# SCH_MCP3008-Raspberry-Pi-3B_-SPI_2025-04.net
KiCad netlist of a schematic drawn in EasyEDA
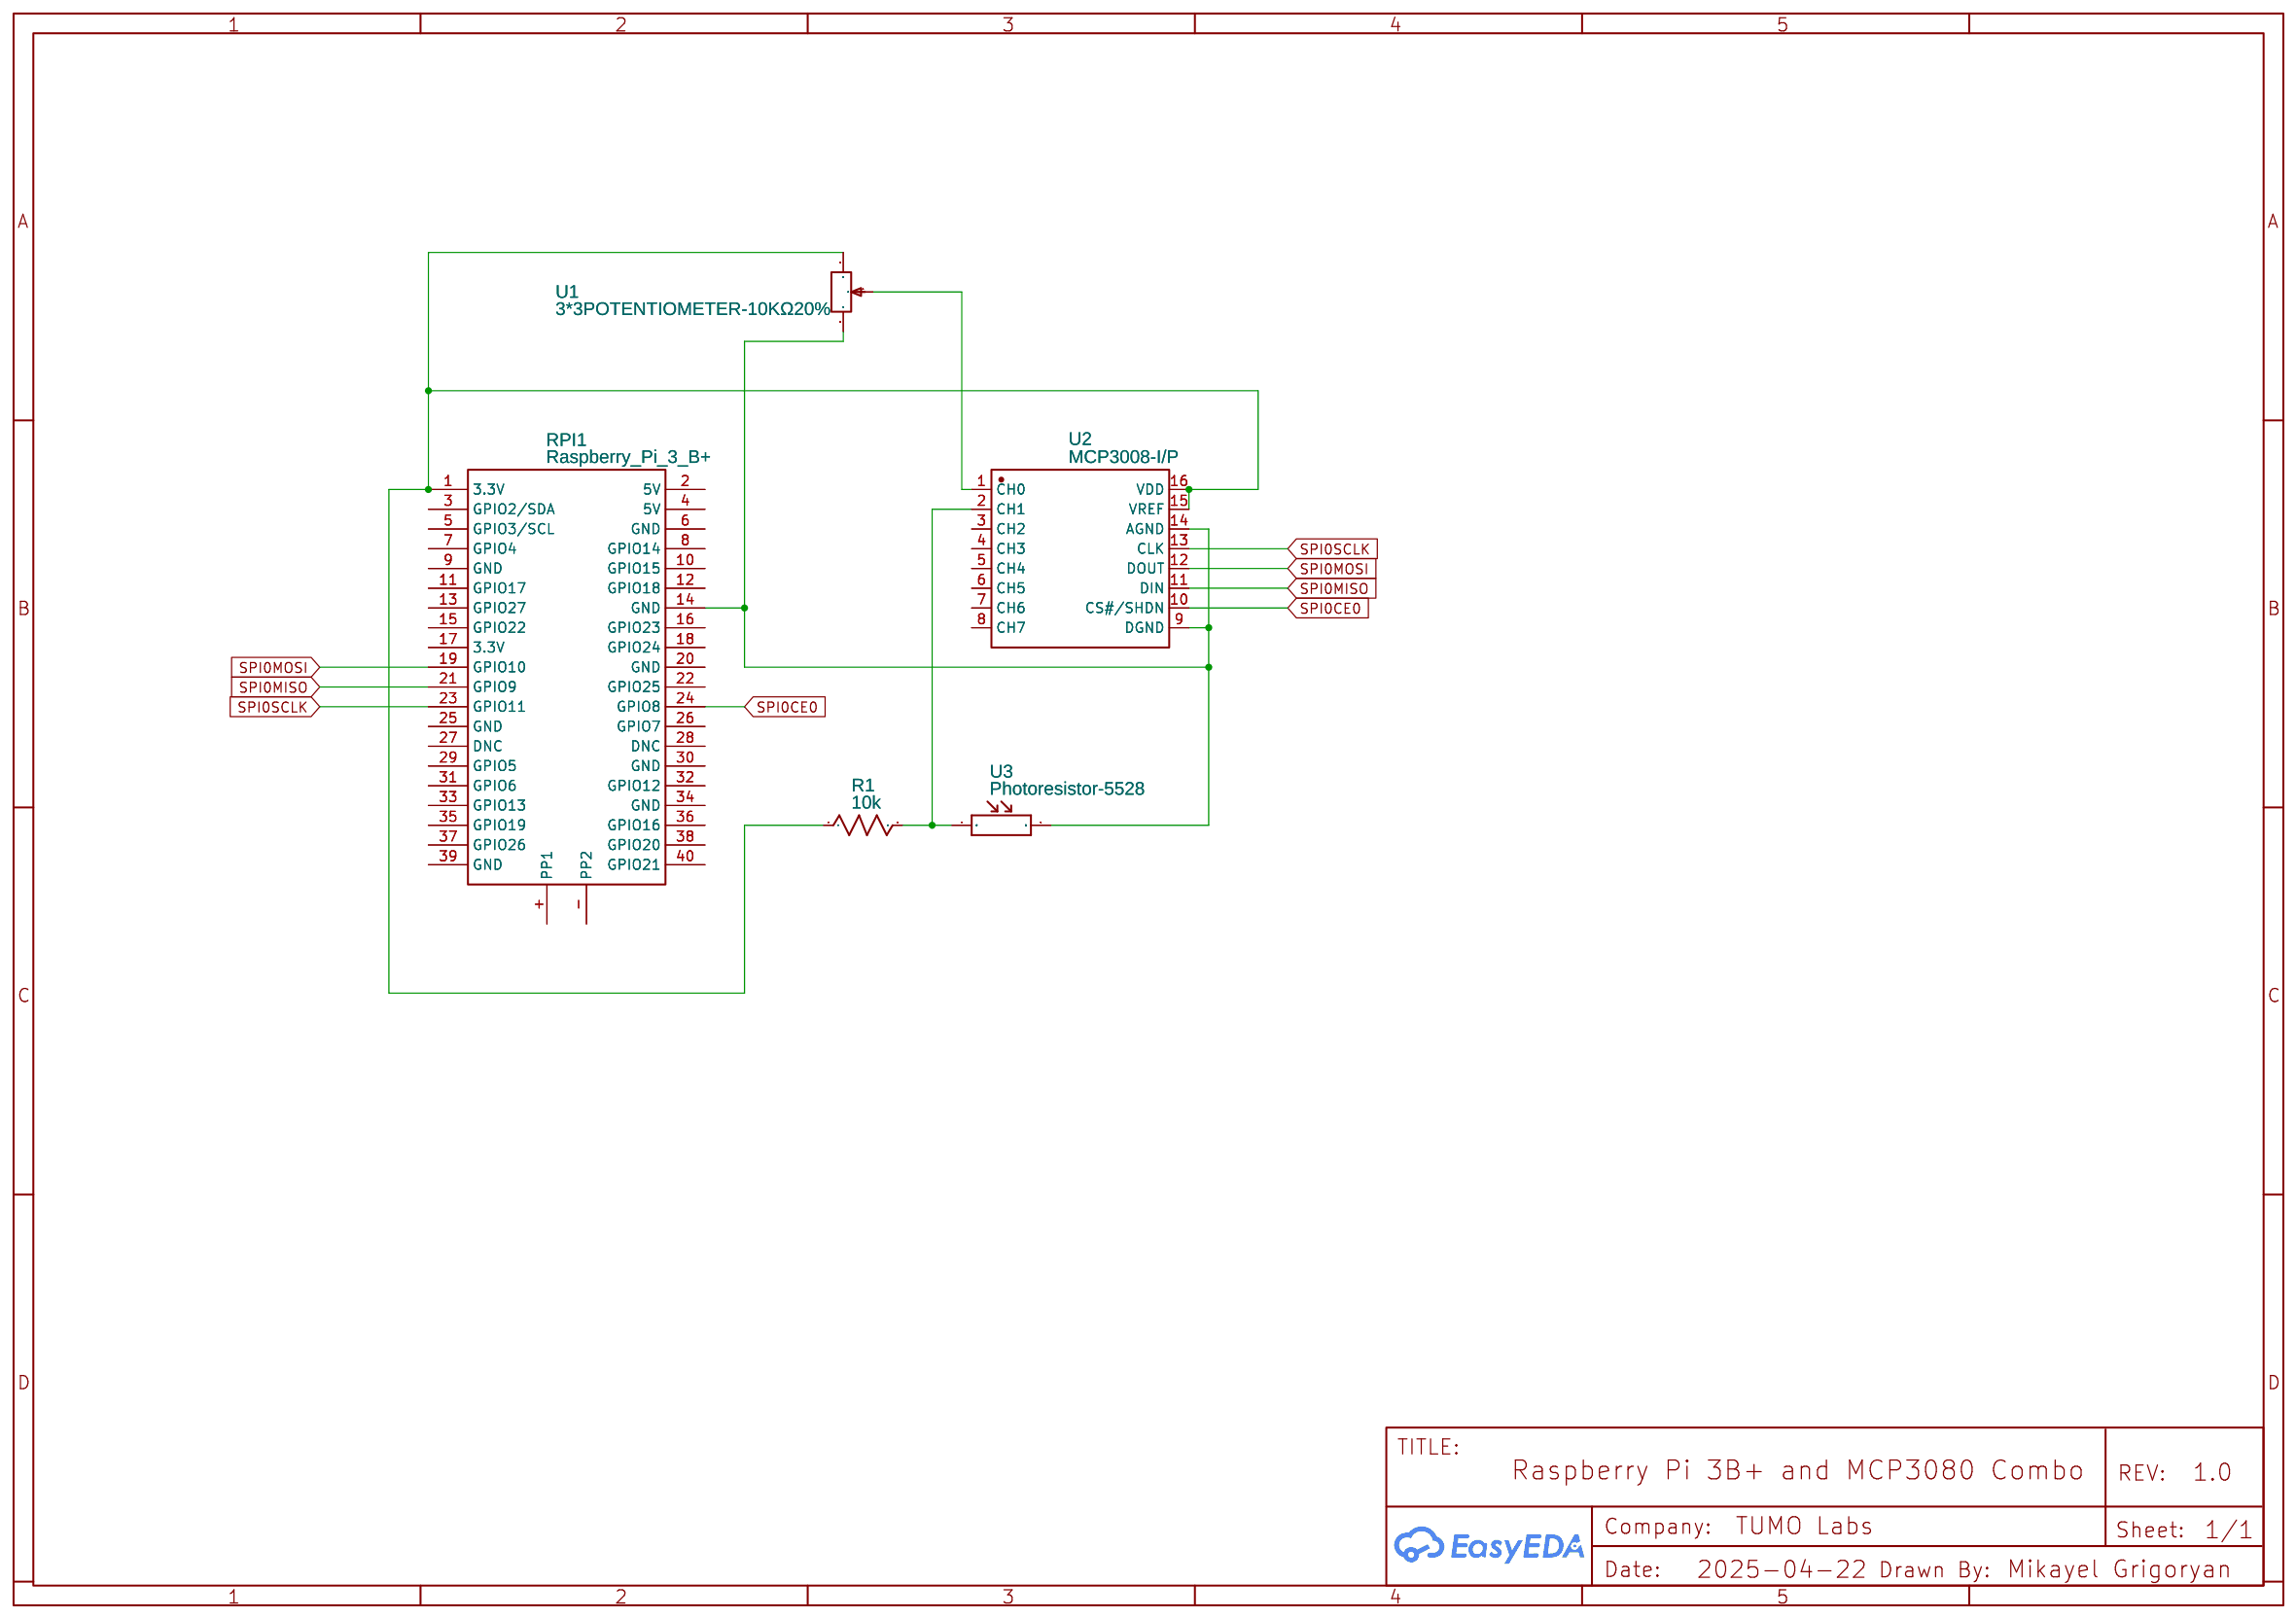
[diagram p0: schematic sheet]

(export (version "E")
  (design (tool "Eeschema 10.0.6"))
  (components
    (comp (ref "R1") (value "10k") (libsource (lib "") (part "R_0603_US")))
    (comp (ref "RPI1")
      (value "Raspberry_Pi_3_B+")
      (fields
        (field (name "Manufacturer Part") "Raspberry Pi 3 - Model B+ - 1.4GHz Cortex-A53 with 1GB RAM")
        (field (name "Manufacturer") "Raspberry Pi")
      )
      (libsource (lib "") (part "Raspberry_Pi_3_B+"))
    )
    (comp (ref "U1")
      (value "3*3POTENTIOMETER-10KΩ20%")
      (fields (field (name "Manufacturer Part") "3*3Potentiometer-10kΩ20%"))
      (libsource (lib "") (part "3*3POTENTIOMETER-10KΩ20%"))
    )
    (comp (ref "U2")
      (value "MCP3008-I/P")
      (fields (field (name "Manufacturer") "MICROCHIP(美国微芯)"))
      (libsource (lib "") (part "MCP3008-I/P"))
    )
    (comp (ref "U3") (value "Photoresistor-5528") (libsource (lib "") (part "Photoresistor-5528")))
  )
  (nets
    (net (code "1") (name "Net-(U2-AGND)") (class "Default")
      (node (ref "RPI1") (pin "14") (pinfunction "GND_14") (pintype "unspecified"))
      (node (ref "U1") (pin "3") (pinfunction "3_3") (pintype "input"))
      (node (ref "U2") (pin "14") (pinfunction "AGND_14") (pintype "unspecified"))
      (node (ref "U2") (pin "9") (pinfunction "DGND_9") (pintype "unspecified"))
      (node (ref "U3") (pin "2") (pinfunction "P$2_2") (pintype "unspecified"))
    )
    (net (code "2") (name "Net-(U2-CH0)") (class "Default")
      (node (ref "U1") (pin "2") (pinfunction "2_2") (pintype "input"))
      (node (ref "U2") (pin "1") (pinfunction "CH0_1") (pintype "unspecified"))
    )
    (net (code "3") (name "Net-(U2-CH1)") (class "Default")
      (node (ref "R1") (pin "2") (pinfunction "2_2") (pintype "unspecified"))
      (node (ref "U2") (pin "2") (pinfunction "CH1_2") (pintype "unspecified"))
      (node (ref "U3") (pin "1") (pinfunction "P$1_1") (pintype "unspecified"))
    )
    (net (code "4") (name "Net-(U2-VDD)") (class "Default")
      (node (ref "R1") (pin "1") (pinfunction "1_1") (pintype "unspecified"))
      (node (ref "RPI1") (pin "1") (pinfunction "3.3V_1") (pintype "passive"))
      (node (ref "U1") (pin "1") (pinfunction "1_1") (pintype "input"))
      (node (ref "U2") (pin "15") (pinfunction "VREF_15") (pintype "unspecified"))
      (node (ref "U2") (pin "16") (pinfunction "VDD_16") (pintype "unspecified"))
    )
    (net (code "5") (name "SPI0CE0") (class "Default")
      (node (ref "RPI1") (pin "24") (pinfunction "GPIO8_24") (pintype "bidirectional"))
      (node (ref "U2") (pin "10") (pinfunction "CS#/SHDN_10") (pintype "unspecified"))
    )
    (net (code "6") (name "SPI0MISO") (class "Default")
      (node (ref "RPI1") (pin "21") (pinfunction "GPIO9_21") (pintype "bidirectional"))
      (node (ref "U2") (pin "11") (pinfunction "DIN_11") (pintype "unspecified"))
    )
    (net (code "7") (name "SPI0MOSI") (class "Default")
      (node (ref "RPI1") (pin "19") (pinfunction "GPIO10_19") (pintype "bidirectional"))
      (node (ref "U2") (pin "12") (pinfunction "DOUT_12") (pintype "unspecified"))
    )
    (net (code "8") (name "SPI0SCLK") (class "Default")
      (node (ref "RPI1") (pin "23") (pinfunction "GPIO11_23") (pintype "bidirectional"))
      (node (ref "U2") (pin "13") (pinfunction "CLK_13") (pintype "unspecified"))
    )
    (net (code "9") (name "unconnected-(RPI1-3.3V-Pad17)") (class "Default")
      (node (ref "RPI1") (pin "17") (pinfunction "3.3V_17") (pintype "passive"))
    )
    (net (code "10") (name "unconnected-(RPI1-5V-Pad2)") (class "Default")
      (node (ref "RPI1") (pin "2") (pinfunction "5V_2") (pintype "passive"))
    )
    (net (code "11") (name "unconnected-(RPI1-5V-Pad4)") (class "Default")
      (node (ref "RPI1") (pin "4") (pinfunction "5V_4") (pintype "passive"))
    )
    (net (code "12") (name "unconnected-(RPI1-DNC-Pad27)") (class "Default")
      (node (ref "RPI1") (pin "27") (pinfunction "DNC_27") (pintype "unspecified"))
    )
    (net (code "13") (name "unconnected-(RPI1-DNC-Pad28)") (class "Default")
      (node (ref "RPI1") (pin "28") (pinfunction "DNC_28") (pintype "unspecified"))
    )
    (net (code "14") (name "unconnected-(RPI1-GND-Pad6)") (class "Default")
      (node (ref "RPI1") (pin "6") (pinfunction "GND_6") (pintype "unspecified"))
    )
    (net (code "15") (name "unconnected-(RPI1-GND-Pad9)") (class "Default")
      (node (ref "RPI1") (pin "9") (pinfunction "GND_9") (pintype "unspecified"))
    )
    (net (code "16") (name "unconnected-(RPI1-GND-Pad20)") (class "Default")
      (node (ref "RPI1") (pin "20") (pinfunction "GND_20") (pintype "unspecified"))
    )
    (net (code "17") (name "unconnected-(RPI1-GND-Pad25)") (class "Default")
      (node (ref "RPI1") (pin "25") (pinfunction "GND_25") (pintype "unspecified"))
    )
    (net (code "18") (name "unconnected-(RPI1-GND-Pad30)") (class "Default")
      (node (ref "RPI1") (pin "30") (pinfunction "GND_30") (pintype "unspecified"))
    )
    (net (code "19") (name "unconnected-(RPI1-GND-Pad34)") (class "Default")
      (node (ref "RPI1") (pin "34") (pinfunction "GND_34") (pintype "unspecified"))
    )
    (net (code "20") (name "unconnected-(RPI1-GND-Pad39)") (class "Default")
      (node (ref "RPI1") (pin "39") (pinfunction "GND_39") (pintype "unspecified"))
    )
    (net (code "21") (name "unconnected-(RPI1-GPIO2{slash}SDA-Pad3)") (class "Default")
      (node (ref "RPI1") (pin "3") (pinfunction "GPIO2/SDA_3") (pintype "bidirectional"))
    )
    (net (code "22") (name "unconnected-(RPI1-GPIO3{slash}SCL-Pad5)") (class "Default")
      (node (ref "RPI1") (pin "5") (pinfunction "GPIO3/SCL_5") (pintype "bidirectional"))
    )
    (net (code "23") (name "unconnected-(RPI1-GPIO4-Pad7)") (class "Default")
      (node (ref "RPI1") (pin "7") (pinfunction "GPIO4_7") (pintype "bidirectional"))
    )
    (net (code "24") (name "unconnected-(RPI1-GPIO5-Pad29)") (class "Default")
      (node (ref "RPI1") (pin "29") (pinfunction "GPIO5_29") (pintype "bidirectional"))
    )
    (net (code "25") (name "unconnected-(RPI1-GPIO6-Pad31)") (class "Default")
      (node (ref "RPI1") (pin "31") (pinfunction "GPIO6_31") (pintype "bidirectional"))
    )
    (net (code "26") (name "unconnected-(RPI1-GPIO7-Pad26)") (class "Default")
      (node (ref "RPI1") (pin "26") (pinfunction "GPIO7_26") (pintype "bidirectional"))
    )
    (net (code "27") (name "unconnected-(RPI1-GPIO12-Pad32)") (class "Default")
      (node (ref "RPI1") (pin "32") (pinfunction "GPIO12_32") (pintype "bidirectional"))
    )
    (net (code "28") (name "unconnected-(RPI1-GPIO13-Pad33)") (class "Default")
      (node (ref "RPI1") (pin "33") (pinfunction "GPIO13_33") (pintype "bidirectional"))
    )
    (net (code "29") (name "unconnected-(RPI1-GPIO14-Pad8)") (class "Default")
      (node (ref "RPI1") (pin "8") (pinfunction "GPIO14_8") (pintype "bidirectional"))
    )
    (net (code "30") (name "unconnected-(RPI1-GPIO15-Pad10)") (class "Default")
      (node (ref "RPI1") (pin "10") (pinfunction "GPIO15_10") (pintype "bidirectional"))
    )
    (net (code "31") (name "unconnected-(RPI1-GPIO16-Pad36)") (class "Default")
      (node (ref "RPI1") (pin "36") (pinfunction "GPIO16_36") (pintype "bidirectional"))
    )
    (net (code "32") (name "unconnected-(RPI1-GPIO17-Pad11)") (class "Default")
      (node (ref "RPI1") (pin "11") (pinfunction "GPIO17_11") (pintype "bidirectional"))
    )
    (net (code "33") (name "unconnected-(RPI1-GPIO18-Pad12)") (class "Default")
      (node (ref "RPI1") (pin "12") (pinfunction "GPIO18_12") (pintype "bidirectional"))
    )
    (net (code "34") (name "unconnected-(RPI1-GPIO19-Pad35)") (class "Default")
      (node (ref "RPI1") (pin "35") (pinfunction "GPIO19_35") (pintype "bidirectional"))
    )
    (net (code "35") (name "unconnected-(RPI1-GPIO20-Pad38)") (class "Default")
      (node (ref "RPI1") (pin "38") (pinfunction "GPIO20_38") (pintype "bidirectional"))
    )
    (net (code "36") (name "unconnected-(RPI1-GPIO21-Pad40)") (class "Default")
      (node (ref "RPI1") (pin "40") (pinfunction "GPIO21_40") (pintype "bidirectional"))
    )
    (net (code "37") (name "unconnected-(RPI1-GPIO22-Pad15)") (class "Default")
      (node (ref "RPI1") (pin "15") (pinfunction "GPIO22_15") (pintype "bidirectional"))
    )
    (net (code "38") (name "unconnected-(RPI1-GPIO23-Pad16)") (class "Default")
      (node (ref "RPI1") (pin "16") (pinfunction "GPIO23_16") (pintype "bidirectional"))
    )
    (net (code "39") (name "unconnected-(RPI1-GPIO24-Pad18)") (class "Default")
      (node (ref "RPI1") (pin "18") (pinfunction "GPIO24_18") (pintype "bidirectional"))
    )
    (net (code "40") (name "unconnected-(RPI1-GPIO25-Pad22)") (class "Default")
      (node (ref "RPI1") (pin "22") (pinfunction "GPIO25_22") (pintype "bidirectional"))
    )
    (net (code "41") (name "unconnected-(RPI1-GPIO26-Pad37)") (class "Default")
      (node (ref "RPI1") (pin "37") (pinfunction "GPIO26_37") (pintype "bidirectional"))
    )
    (net (code "42") (name "unconnected-(RPI1-GPIO27-Pad13)") (class "Default")
      (node (ref "RPI1") (pin "13") (pinfunction "GPIO27_13") (pintype "bidirectional"))
    )
    (net (code "43") (name "unconnected-(RPI1-PP1-Pad+)") (class "Default")
      (node (ref "RPI1") (pin "+") (pinfunction "PP1_+") (pintype "unspecified"))
    )
    (net (code "44") (name "unconnected-(RPI1-PP2-Pad-)") (class "Default")
      (node (ref "RPI1") (pin "-") (pinfunction "PP2_-") (pintype "unspecified"))
    )
    (net (code "45") (name "unconnected-(U2-CH2-Pad3)") (class "Default")
      (node (ref "U2") (pin "3") (pinfunction "CH2_3") (pintype "unspecified"))
    )
    (net (code "46") (name "unconnected-(U2-CH3-Pad4)") (class "Default")
      (node (ref "U2") (pin "4") (pinfunction "CH3_4") (pintype "unspecified"))
    )
    (net (code "47") (name "unconnected-(U2-CH4-Pad5)") (class "Default")
      (node (ref "U2") (pin "5") (pinfunction "CH4_5") (pintype "unspecified"))
    )
    (net (code "48") (name "unconnected-(U2-CH5-Pad6)") (class "Default")
      (node (ref "U2") (pin "6") (pinfunction "CH5_6") (pintype "unspecified"))
    )
    (net (code "49") (name "unconnected-(U2-CH6-Pad7)") (class "Default")
      (node (ref "U2") (pin "7") (pinfunction "CH6_7") (pintype "unspecified"))
    )
    (net (code "50") (name "unconnected-(U2-CH7-Pad8)") (class "Default")
      (node (ref "U2") (pin "8") (pinfunction "CH7_8") (pintype "unspecified"))
    )
  )
)
